# ETR_CELLMETER_CELL_HOLDER.net
KiCad netlist of a schematic drawn in Altium Designer
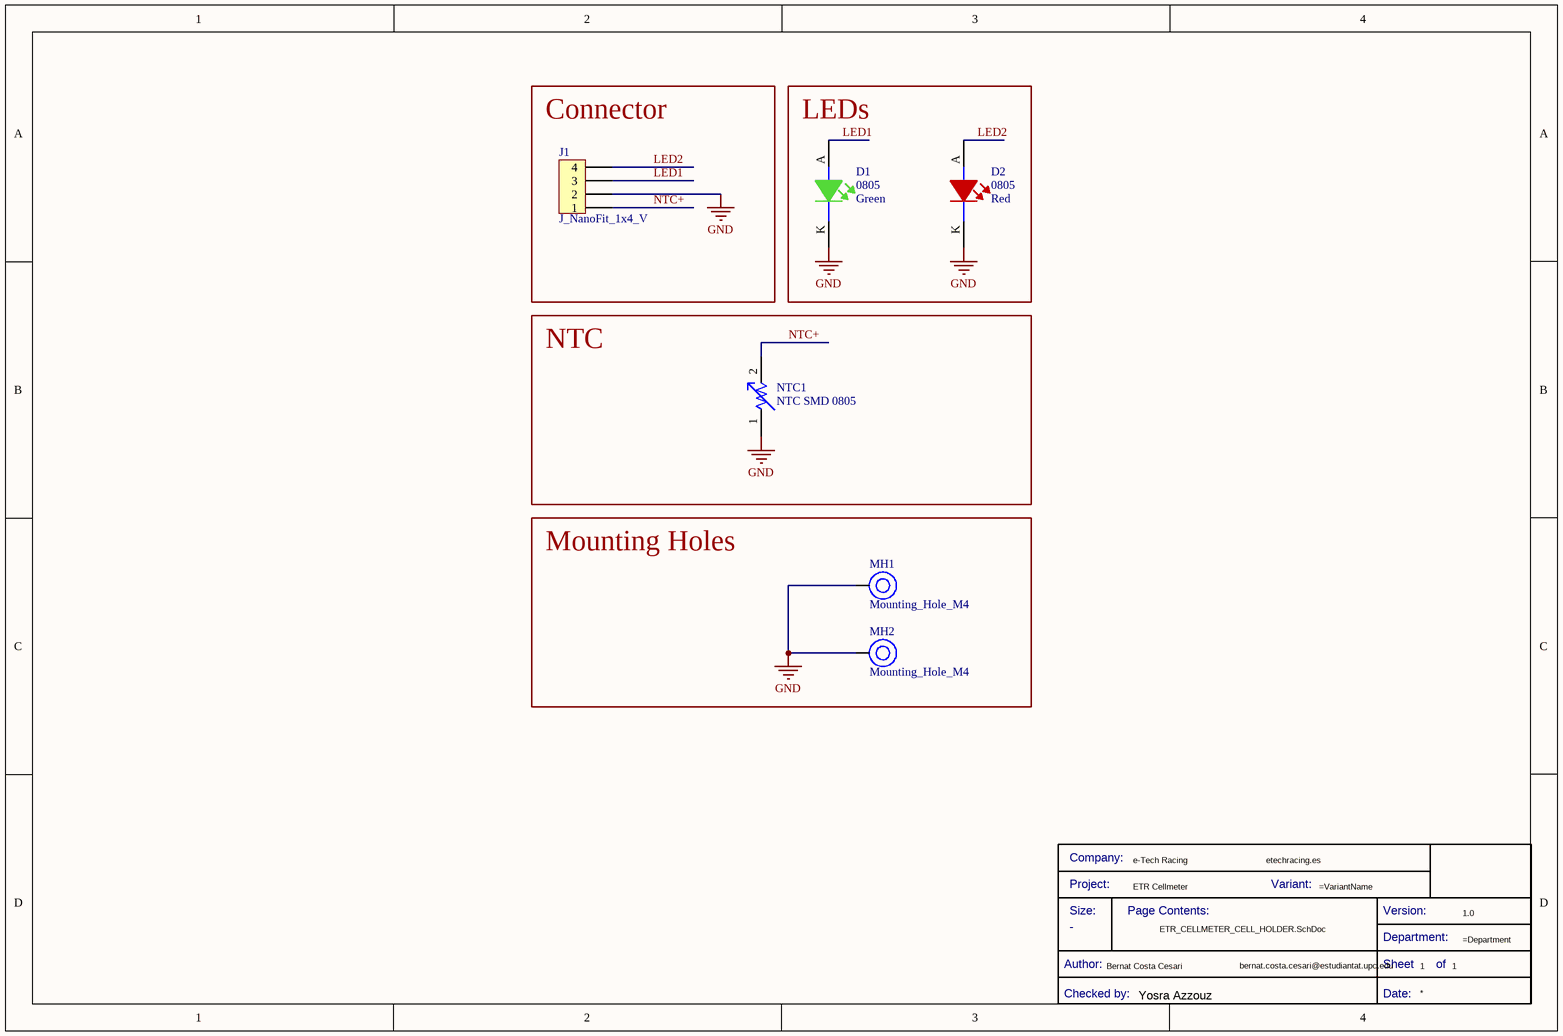
[diagram p0: ETR_CELLMETER_CELL_HOLDER.SchDoc]

(export (version "E")
  (design (tool "Eeschema 10.0.6"))
  (components
    (comp (ref "*")
      (value "Title Block_template")
      (description "Standard Title Block")
      (fields
        (field (name "SIZE") "-")
        (field (name ".CREATOR") "GP")
        (field (name ".PCBCHECK") "GP")
        (field (name ".SCHCHECK") "GP")
      )
      (libsource (lib "EMEA- E-Tech Racing- I'Escola d'Enginyeria de Barcelona Est") (part "Title Block_template"))
    )
    (comp (ref "D1")
      (value "0805")
      (footprint "LED_0805_WE")
      (description "Led, Green, 520 Nm, 3.2 V, 30 Ma, 450 Mcd Rohs Compliant: Yes")
      (fields (field (name "COLOR") "Green") (field (name ".CREATOR") "GP"))
      (libsource (lib "EMEA- E-Tech Racing- I'Escola d'Enginyeria de Barcelona Est") (part "LEDGS-2214-1200"))
    )
    (comp (ref "D2")
      (value "0805")
      (footprint "LED_0805_WE")
      (description "0805(H=0.8mm) 红色 高亮 λD=625nm VF=2V IF=30mA PD=72mW")
      (fields (field (name "COLOR") "Red") (field (name ".CREATOR") "DR"))
      (libsource (lib "EMEA- E-Tech Racing- I'Escola d'Enginyeria de Barcelona Est") (part "LEDRS-1206-1100-Reverse"))
    )
    (comp (ref "J1")
      (value "J_NanoFit_1x4_V")
      (footprint "J_NanoFit_1x4_V")
      (description "Nano-Fit Vertical Header Through Hole 2.50mm Pitch Single Row 4 Circuits with Kinked Pins 0.38")
      (fields (field (name ".CREATOR") "DO"))
      (libsource (lib "EMEA- E-Tech Racing- I'Escola d'Enginyeria de Barcelona Est") (part "J_NanoFit_1x4_V_W"))
    )
    (comp (ref "MH1")
      (value "Mounting_Hole_M4")
      (footprint "Mounting_Hole_M4")
      (description "Mounting Hole M4")
      (libsource (lib "EMEA- E-Tech Racing- I'Escola d'Enginyeria de Barcelona Est") (part "Mounting_Hole_M4"))
    )
    (comp (ref "MH2")
      (value "Mounting_Hole_M4")
      (footprint "Mounting_Hole_M4")
      (description "Mounting Hole M4")
      (libsource (lib "EMEA- E-Tech Racing- I'Escola d'Enginyeria de Barcelona Est") (part "Mounting_Hole_M4"))
    )
    (comp (ref "NTC1")
      (value "NTC SMD 0805")
      (footprint "RESC2012X10N")
      (description "NTC 0805 package 10kR")
      (libsource (lib "EMEA- E-Tech Racing- I'Escola d'Enginyeria de Barcelona Est") (part "0805"))
    )
  )
  (nets
    (net (code "1") (name "/LED1") (class "Default")
      (node (ref "D1") (pin "A") (pinfunction "A_A") (pintype "passive"))
      (node (ref "J1") (pin "3") (pinfunction "3_3") (pintype "passive"))
    )
    (net (code "2") (name "/LED2") (class "Default")
      (node (ref "D2") (pin "A") (pinfunction "A_A") (pintype "passive"))
      (node (ref "J1") (pin "4") (pinfunction "4_4") (pintype "passive"))
    )
    (net (code "3") (name "/NTC+") (class "Default")
      (node (ref "J1") (pin "1") (pinfunction "1_1") (pintype "passive"))
      (node (ref "NTC1") (pin "2") (pinfunction "2_2") (pintype "passive"))
    )
    (net (code "4") (name "GND") (class "Default")
      (node (ref "D1") (pin "K") (pinfunction "K_K") (pintype "passive"))
      (node (ref "D2") (pin "K") (pinfunction "K_K") (pintype "passive"))
      (node (ref "J1") (pin "2") (pinfunction "2_2") (pintype "passive"))
      (node (ref "MH1") (pin "1") (pinfunction "1_1") (pintype "passive"))
      (node (ref "MH2") (pin "1") (pinfunction "1_1") (pintype "passive"))
      (node (ref "NTC1") (pin "1") (pinfunction "1_1") (pintype "passive"))
    )
  )
)
